# Fonte_e_Conex_o.net
KiCad netlist of a schematic drawn in EAGLE
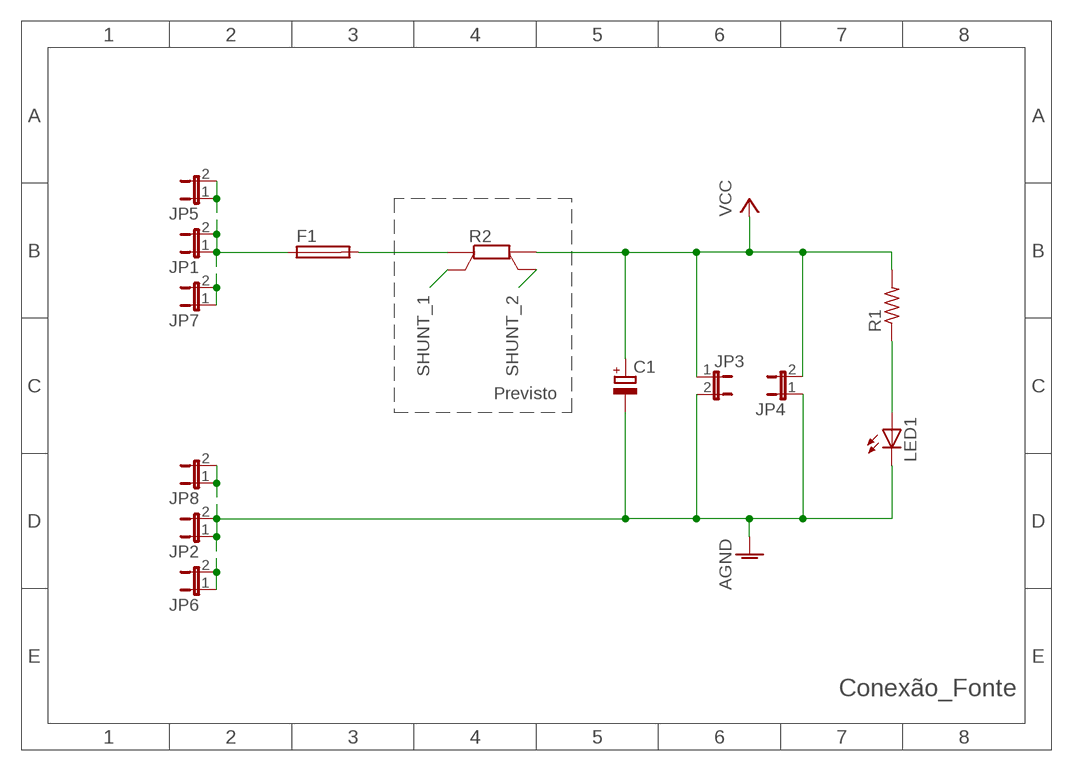
[diagram p0: schematic, sheet 1]

(export (version "E")
  (design (tool "Eeschema 10.0.6"))
  (components
    (comp (ref "C1")
      (value "CPOL-EUE3.5-10")
      (footprint "eagle-import:E3,5-10")
      (libsource (lib "eagle-import") (part "CPOL-EUE3.5-10"))
    )
    (comp (ref "F1")
      (value "KS9V")
      (footprint "eagle-import:KS9V")
      (libsource (lib "eagle-import") (part "KS9V"))
    )
    (comp (ref "JP1")
      (value "JP1E")
      (footprint "eagle-import:JP1")
      (libsource (lib "eagle-import") (part "JP1E"))
    )
    (comp (ref "JP2")
      (value "JP1E")
      (footprint "eagle-import:JP1")
      (libsource (lib "eagle-import") (part "JP1E"))
    )
    (comp (ref "JP3")
      (value "JP1E")
      (footprint "eagle-import:JP1")
      (libsource (lib "eagle-import") (part "JP1E"))
    )
    (comp (ref "JP4")
      (value "JP1E")
      (footprint "eagle-import:JP1")
      (libsource (lib "eagle-import") (part "JP1E"))
    )
    (comp (ref "JP5")
      (value "JP1E")
      (footprint "eagle-import:JP1")
      (libsource (lib "eagle-import") (part "JP1E"))
    )
    (comp (ref "JP6")
      (value "JP1E")
      (footprint "eagle-import:JP1")
      (libsource (lib "eagle-import") (part "JP1E"))
    )
    (comp (ref "JP7")
      (value "JP1E")
      (footprint "eagle-import:JP1")
      (libsource (lib "eagle-import") (part "JP1E"))
    )
    (comp (ref "JP8")
      (value "JP1E")
      (footprint "eagle-import:JP1")
      (libsource (lib "eagle-import") (part "JP1E"))
    )
    (comp (ref "LED1")
      (value "LED3MM")
      (footprint "eagle-import:LED3MM")
      (libsource (lib "eagle-import") (part "LED3MM"))
    )
    (comp (ref "R1")
      (value "R-US_0613/5V")
      (footprint "eagle-import:P0613V")
      (libsource (lib "eagle-import") (part "R-US_0613/5V"))
    )
    (comp (ref "R2")
      (value "PMA-B")
      (footprint "eagle-import:PMA-B")
      (libsource (lib "eagle-import") (part "PMA-B"))
    )
  )
  (nets
    (net (code "1") (name "/SHUNT_1") (class "Default")
      (node (ref "R2") (pin "SB") (pinfunction "SB_SB") (pintype "passive"))
    )
    (net (code "2") (name "/SHUNT_2") (class "Default")
      (node (ref "R2") (pin "SA") (pinfunction "SA_SA") (pintype "passive"))
    )
    (net (code "3") (name "AGND") (class "Default")
      (node (ref "C1") (pin "-") (pinfunction "-_-") (pintype "passive"))
      (node (ref "JP2") (pin "1") (pinfunction "1_1") (pintype "passive"))
      (node (ref "JP2") (pin "2") (pinfunction "2_2") (pintype "passive"))
      (node (ref "JP3") (pin "2") (pinfunction "2_2") (pintype "passive"))
      (node (ref "JP4") (pin "1") (pinfunction "1_1") (pintype "passive"))
      (node (ref "JP6") (pin "1") (pinfunction "1_1") (pintype "passive"))
      (node (ref "JP6") (pin "2") (pinfunction "2_2") (pintype "passive"))
      (node (ref "JP8") (pin "1") (pinfunction "1_1") (pintype "passive"))
      (node (ref "JP8") (pin "2") (pinfunction "2_2") (pintype "passive"))
      (node (ref "LED1") (pin "K") (pinfunction "C_K") (pintype "passive"))
    )
    (net (code "4") (name "Net-(F1-Pad1)") (class "Default")
      (node (ref "F1") (pin "1") (pinfunction "1_1") (pintype "passive"))
      (node (ref "JP1") (pin "1") (pinfunction "1_1") (pintype "passive"))
      (node (ref "JP1") (pin "2") (pinfunction "2_2") (pintype "passive"))
      (node (ref "JP5") (pin "1") (pinfunction "1_1") (pintype "passive"))
      (node (ref "JP5") (pin "2") (pinfunction "2_2") (pintype "passive"))
      (node (ref "JP7") (pin "1") (pinfunction "1_1") (pintype "passive"))
      (node (ref "JP7") (pin "2") (pinfunction "2_2") (pintype "passive"))
    )
    (net (code "5") (name "Net-(F1-Pad2)") (class "Default")
      (node (ref "F1") (pin "2") (pinfunction "2_2") (pintype "passive"))
      (node (ref "R2") (pin "B") (pinfunction "B_B") (pintype "passive"))
    )
    (net (code "6") (name "Net-(LED1-PadA)") (class "Default")
      (node (ref "LED1") (pin "A") (pinfunction "A_A") (pintype "passive"))
      (node (ref "R1") (pin "1") (pinfunction "1_1") (pintype "passive"))
    )
    (net (code "7") (name "VCC") (class "Default")
      (node (ref "C1") (pin "+") (pinfunction "+_+") (pintype "passive"))
      (node (ref "JP3") (pin "1") (pinfunction "1_1") (pintype "passive"))
      (node (ref "JP4") (pin "2") (pinfunction "2_2") (pintype "passive"))
      (node (ref "R1") (pin "2") (pinfunction "2_2") (pintype "passive"))
      (node (ref "R2") (pin "A") (pinfunction "A_A") (pintype "passive"))
    )
  )
)
